# darwin-atlas-module.net
KiCad netlist of a schematic drawn in EAGLE
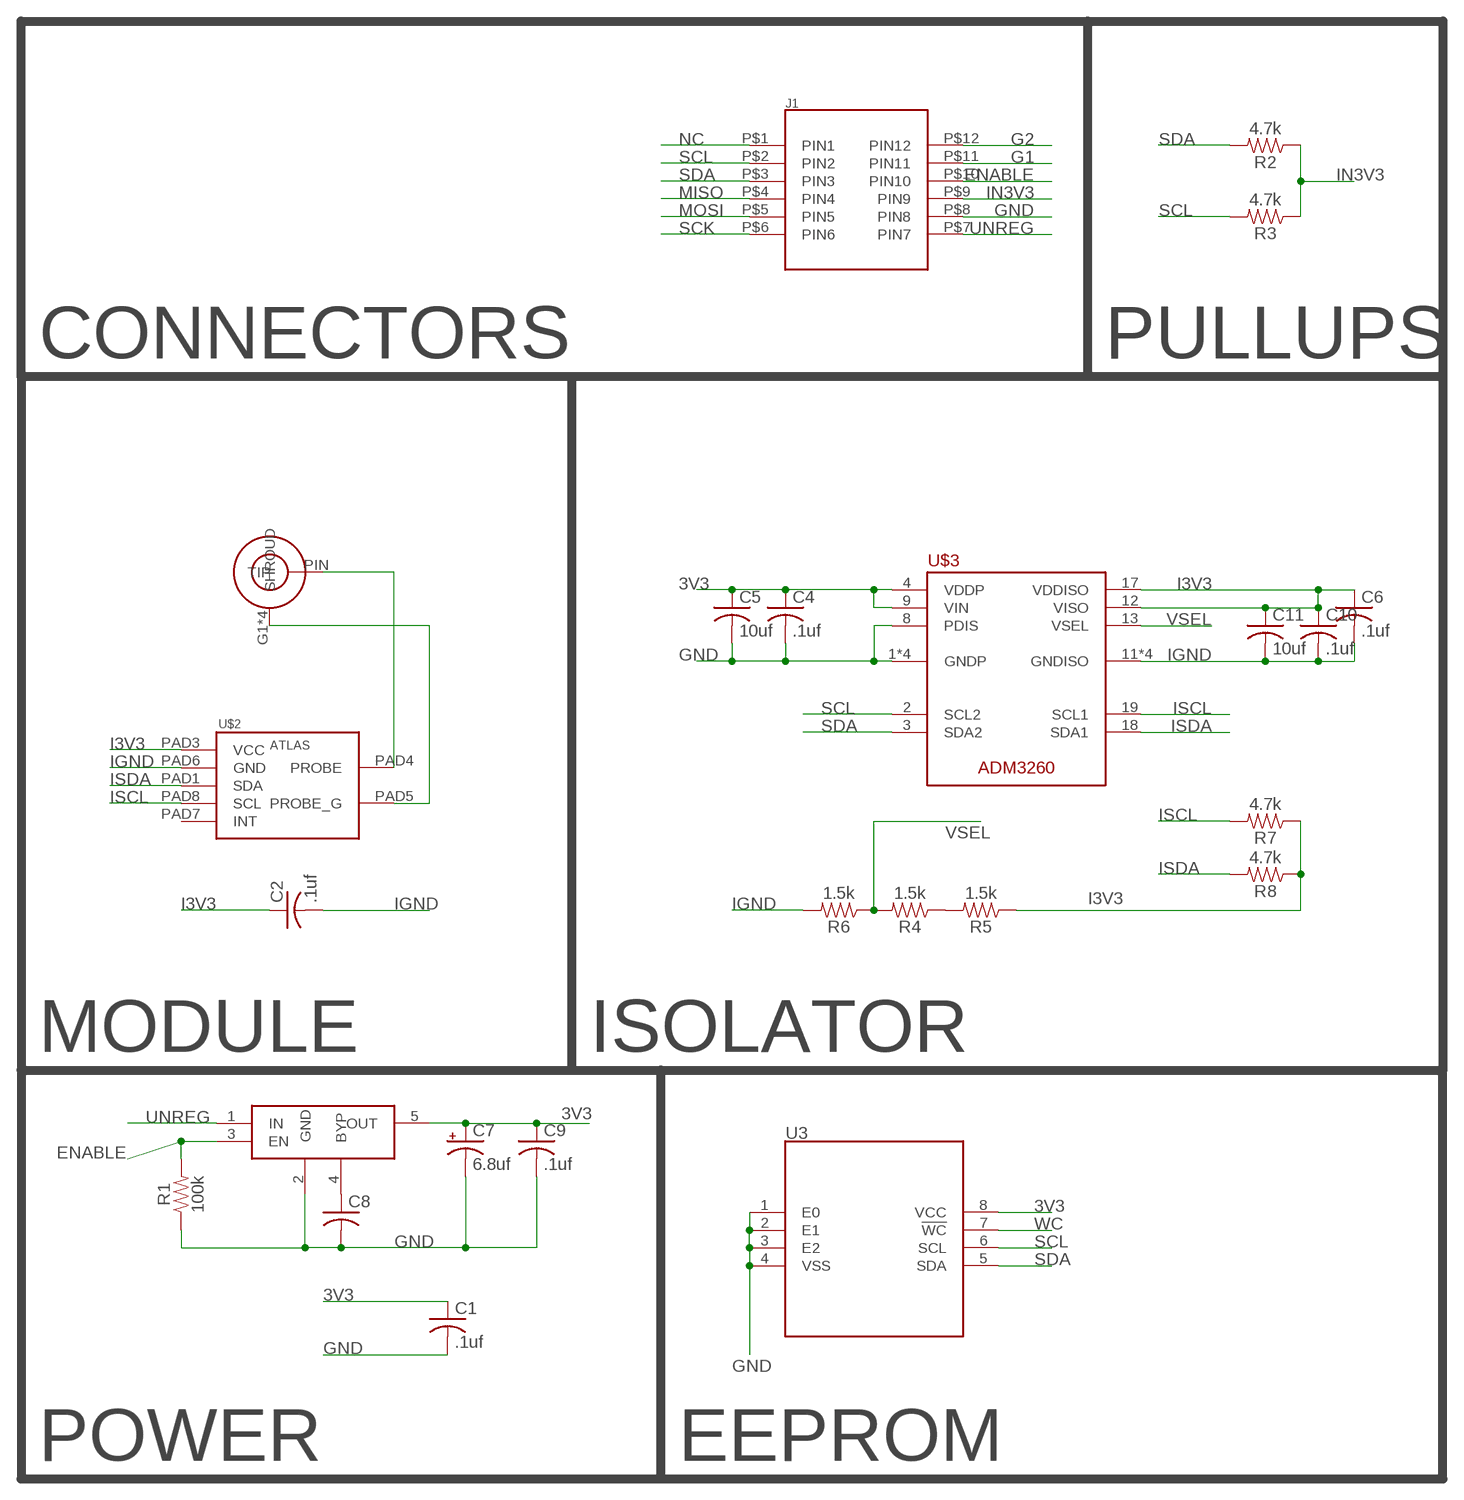
[diagram p0: schematic, sheet 1]

(export (version "E")
  (design (tool "Eeschema 10.0.6"))
  (components
    (comp (ref "C1")
      (value ".1uf")
      (footprint "eagle-import:C0603K")
      (libsource (lib "eagle-import") (part "C-USC0603K"))
    )
    (comp (ref "C2")
      (value ".1uf")
      (footprint "eagle-import:C0603K")
      (libsource (lib "eagle-import") (part "C-USC0603K"))
    )
    (comp (ref "C4")
      (value ".1uf")
      (footprint "eagle-import:C0603K")
      (libsource (lib "eagle-import") (part "C-USC0603K"))
    )
    (comp (ref "C5")
      (value "10uf")
      (footprint "eagle-import:C0603K")
      (libsource (lib "eagle-import") (part "C-USC0603K"))
    )
    (comp (ref "C6")
      (value ".1uf")
      (footprint "eagle-import:C0603K")
      (libsource (lib "eagle-import") (part "C-USC0603K"))
    )
    (comp (ref "C7")
      (value "6.8uf")
      (footprint "eagle-import:A_3216-18R")
      (libsource (lib "eagle-import") (part "CPOL-USA/3216-18R"))
    )
    (comp (ref "C8")
      (value "C-USC0603K")
      (footprint "eagle-import:C0603K")
      (libsource (lib "eagle-import") (part "C-USC0603K"))
    )
    (comp (ref "C9")
      (value ".1uf")
      (footprint "eagle-import:C0603K")
      (libsource (lib "eagle-import") (part "C-USC0603K"))
    )
    (comp (ref "C10")
      (value ".1uf")
      (footprint "eagle-import:C0603K")
      (libsource (lib "eagle-import") (part "C-USC0603K"))
    )
    (comp (ref "C11")
      (value "10uf")
      (footprint "eagle-import:C0603K")
      (libsource (lib "eagle-import") (part "C-USC0603K"))
    )
    (comp (ref "J1")
      (value "2X6-HEADERS")
      (footprint "eagle-import:M20-7810645")
      (libsource (lib "eagle-import") (part "2X6-HEADERS"))
    )
    (comp (ref "R1")
      (value "100k")
      (footprint "eagle-import:0603")
      (libsource (lib "eagle-import") (part "100KOHM-0603-1/10W-1%"))
    )
    (comp (ref "R2")
      (value "4.7k")
      (footprint "eagle-import:0603")
      (libsource (lib "eagle-import") (part "100KOHM-0603-1/10W-1%"))
    )
    (comp (ref "R3")
      (value "4.7k")
      (footprint "eagle-import:0603")
      (libsource (lib "eagle-import") (part "100KOHM-0603-1/10W-1%"))
    )
    (comp (ref "R4")
      (value "1.5k")
      (footprint "eagle-import:0603")
      (libsource (lib "eagle-import") (part "100KOHM-0603-1/10W-1%"))
    )
    (comp (ref "R5")
      (value "1.5k")
      (footprint "eagle-import:0603")
      (libsource (lib "eagle-import") (part "100KOHM-0603-1/10W-1%"))
    )
    (comp (ref "R6")
      (value "1.5k")
      (footprint "eagle-import:0603")
      (libsource (lib "eagle-import") (part "100KOHM-0603-1/10W-1%"))
    )
    (comp (ref "R7")
      (value "4.7k")
      (footprint "eagle-import:0603")
      (libsource (lib "eagle-import") (part "100KOHM-0603-1/10W-1%"))
    )
    (comp (ref "R8")
      (value "4.7k")
      (footprint "eagle-import:0603")
      (libsource (lib "eagle-import") (part "100KOHM-0603-1/10W-1%"))
    )
    (comp (ref "U$1")
      (value "5-1814832-1")
      (footprint "eagle-import:5-1814832-1")
      (libsource (lib "eagle-import") (part "5-1814832-1"))
    )
    (comp (ref "U$2")
      (value "ATLAS10P")
      (footprint "eagle-import:ATLAS-10P")
      (libsource (lib "eagle-import") (part "ATLAS10P"))
    )
    (comp (ref "U$3")
      (value "ADM3260")
      (footprint "eagle-import:SOP65P780X200-20")
      (libsource (lib "eagle-import") (part "ADM3260"))
    )
    (comp (ref "U$4")
      (value "MIC5219-3.3YM5-TR")
      (footprint "eagle-import:SOT95P280X145-5")
      (libsource (lib "eagle-import") (part "MIC5219-3.3YM5-TR"))
    )
    (comp (ref "U3")
      (value "M24C02-WMN6TP")
      (footprint "eagle-import:SOIC127P600X175-8")
      (libsource (lib "eagle-import") (part "M24C02-WMN6TP"))
    )
  )
  (nets
    (net (code "1") (name "/3V3") (class "Default")
      (node (ref "C1") (pin "1") (pinfunction "1_1") (pintype "passive"))
      (node (ref "C4") (pin "1") (pinfunction "1_1") (pintype "passive"))
      (node (ref "C5") (pin "1") (pinfunction "1_1") (pintype "passive"))
      (node (ref "C7") (pin "+") (pinfunction "+_+") (pintype "passive"))
      (node (ref "C9") (pin "1") (pinfunction "1_1") (pintype "passive"))
      (node (ref "U$3") (pin "4") (pinfunction "VDDP_4") (pintype "bidirectional"))
      (node (ref "U$3") (pin "9") (pinfunction "VIN_9") (pintype "bidirectional"))
      (node (ref "U$4") (pin "5") (pinfunction "OUT_5") (pintype "bidirectional"))
      (node (ref "U3") (pin "8") (pinfunction "VCC_8") (pintype "bidirectional"))
    )
    (net (code "2") (name "/ENABLE") (class "Default")
      (node (ref "J1") (pin "P$10") (pinfunction "PIN10_P$10") (pintype "bidirectional"))
      (node (ref "R1") (pin "2") (pinfunction "2_2") (pintype "passive"))
      (node (ref "U$4") (pin "3") (pinfunction "EN_3") (pintype "bidirectional"))
    )
    (net (code "3") (name "/G1") (class "Default")
      (node (ref "J1") (pin "P$11") (pinfunction "PIN11_P$11") (pintype "bidirectional"))
    )
    (net (code "4") (name "/G2") (class "Default")
      (node (ref "J1") (pin "P$12") (pinfunction "PIN12_P$12") (pintype "bidirectional"))
    )
    (net (code "5") (name "/GND") (class "Default")
      (node (ref "C1") (pin "2") (pinfunction "2_2") (pintype "passive"))
      (node (ref "C4") (pin "2") (pinfunction "2_2") (pintype "passive"))
      (node (ref "C5") (pin "2") (pinfunction "2_2") (pintype "passive"))
      (node (ref "C7") (pin "-") (pinfunction "-_-") (pintype "passive"))
      (node (ref "C8") (pin "2") (pinfunction "2_2") (pintype "passive"))
      (node (ref "C9") (pin "2") (pinfunction "2_2") (pintype "passive"))
      (node (ref "J1") (pin "P$8") (pinfunction "PIN8_P$8") (pintype "bidirectional"))
      (node (ref "R1") (pin "1") (pinfunction "1_1") (pintype "passive"))
      (node (ref "U$3") (pin "1") (pinfunction "GNDP_1") (pintype "bidirectional"))
      (node (ref "U$3") (pin "10") (pinfunction "GNDP_10") (pintype "bidirectional"))
      (node (ref "U$3") (pin "5") (pinfunction "GNDP_5") (pintype "bidirectional"))
      (node (ref "U$3") (pin "7") (pinfunction "GNDP_7") (pintype "bidirectional"))
      (node (ref "U$3") (pin "8") (pinfunction "PDIS_8") (pintype "bidirectional"))
      (node (ref "U$4") (pin "2") (pinfunction "GND_2") (pintype "bidirectional"))
      (node (ref "U3") (pin "1") (pinfunction "E0_1") (pintype "bidirectional"))
      (node (ref "U3") (pin "2") (pinfunction "E1_2") (pintype "bidirectional"))
      (node (ref "U3") (pin "3") (pinfunction "E2_3") (pintype "bidirectional"))
      (node (ref "U3") (pin "4") (pinfunction "VSS_4") (pintype "bidirectional"))
    )
    (net (code "6") (name "/I3V3") (class "Default")
      (node (ref "C10") (pin "1") (pinfunction "1_1") (pintype "passive"))
      (node (ref "C11") (pin "1") (pinfunction "1_1") (pintype "passive"))
      (node (ref "C2") (pin "1") (pinfunction "1_1") (pintype "passive"))
      (node (ref "C6") (pin "1") (pinfunction "1_1") (pintype "passive"))
      (node (ref "R5") (pin "1") (pinfunction "1_1") (pintype "passive"))
      (node (ref "R7") (pin "1") (pinfunction "1_1") (pintype "passive"))
      (node (ref "R8") (pin "1") (pinfunction "1_1") (pintype "passive"))
      (node (ref "U$2") (pin "PAD3") (pinfunction "VCC_PAD3") (pintype "bidirectional"))
      (node (ref "U$3") (pin "12") (pinfunction "VISO_12") (pintype "bidirectional"))
      (node (ref "U$3") (pin "17") (pinfunction "VDDISO_17") (pintype "bidirectional"))
    )
    (net (code "7") (name "/IGND") (class "Default")
      (node (ref "C10") (pin "2") (pinfunction "2_2") (pintype "passive"))
      (node (ref "C11") (pin "2") (pinfunction "2_2") (pintype "passive"))
      (node (ref "C2") (pin "2") (pinfunction "2_2") (pintype "passive"))
      (node (ref "C6") (pin "2") (pinfunction "2_2") (pintype "passive"))
      (node (ref "R6") (pin "2") (pinfunction "2_2") (pintype "passive"))
      (node (ref "U$2") (pin "PAD6") (pinfunction "GND_PAD6") (pintype "bidirectional"))
      (node (ref "U$3") (pin "11") (pinfunction "GNDISO_11") (pintype "bidirectional"))
      (node (ref "U$3") (pin "14") (pinfunction "GNDISO_14") (pintype "bidirectional"))
      (node (ref "U$3") (pin "16") (pinfunction "GNDISO_16") (pintype "bidirectional"))
      (node (ref "U$3") (pin "20") (pinfunction "GNDISO_20") (pintype "bidirectional"))
    )
    (net (code "8") (name "/IN3V3") (class "Default")
      (node (ref "J1") (pin "P$9") (pinfunction "PIN9_P$9") (pintype "bidirectional"))
      (node (ref "R2") (pin "1") (pinfunction "1_1") (pintype "passive"))
      (node (ref "R3") (pin "1") (pinfunction "1_1") (pintype "passive"))
    )
    (net (code "9") (name "/ISCL") (class "Default")
      (node (ref "R7") (pin "2") (pinfunction "2_2") (pintype "passive"))
      (node (ref "U$2") (pin "PAD8") (pinfunction "SCL_PAD8") (pintype "bidirectional"))
      (node (ref "U$3") (pin "19") (pinfunction "SCL1_19") (pintype "bidirectional"))
    )
    (net (code "10") (name "/ISDA") (class "Default")
      (node (ref "R8") (pin "2") (pinfunction "2_2") (pintype "passive"))
      (node (ref "U$2") (pin "PAD1") (pinfunction "SDA_PAD1") (pintype "bidirectional"))
      (node (ref "U$3") (pin "18") (pinfunction "SDA1_18") (pintype "bidirectional"))
    )
    (net (code "11") (name "/MISO") (class "Default")
      (node (ref "J1") (pin "P$4") (pinfunction "PIN4_P$4") (pintype "bidirectional"))
    )
    (net (code "12") (name "/MOSI") (class "Default")
      (node (ref "J1") (pin "P$5") (pinfunction "PIN5_P$5") (pintype "bidirectional"))
    )
    (net (code "13") (name "/NC") (class "Default")
      (node (ref "J1") (pin "P$1") (pinfunction "PIN1_P$1") (pintype "bidirectional"))
    )
    (net (code "14") (name "/SCK") (class "Default")
      (node (ref "J1") (pin "P$6") (pinfunction "PIN6_P$6") (pintype "bidirectional"))
    )
    (net (code "15") (name "/SCL") (class "Default")
      (node (ref "J1") (pin "P$2") (pinfunction "PIN2_P$2") (pintype "bidirectional"))
      (node (ref "R3") (pin "2") (pinfunction "2_2") (pintype "passive"))
      (node (ref "U$3") (pin "2") (pinfunction "SCL2_2") (pintype "bidirectional"))
      (node (ref "U3") (pin "6") (pinfunction "SCL_6") (pintype "bidirectional"))
    )
    (net (code "16") (name "/SDA") (class "Default")
      (node (ref "J1") (pin "P$3") (pinfunction "PIN3_P$3") (pintype "bidirectional"))
      (node (ref "R2") (pin "2") (pinfunction "2_2") (pintype "passive"))
      (node (ref "U$3") (pin "3") (pinfunction "SDA2_3") (pintype "bidirectional"))
      (node (ref "U3") (pin "5") (pinfunction "SDA_5") (pintype "bidirectional"))
    )
    (net (code "17") (name "/UNREG") (class "Default")
      (node (ref "J1") (pin "P$7") (pinfunction "PIN7_P$7") (pintype "bidirectional"))
      (node (ref "U$4") (pin "1") (pinfunction "IN_1") (pintype "bidirectional"))
    )
    (net (code "18") (name "/VSEL") (class "Default")
      (node (ref "R4") (pin "2") (pinfunction "2_2") (pintype "passive"))
      (node (ref "R6") (pin "1") (pinfunction "1_1") (pintype "passive"))
      (node (ref "U$3") (pin "13") (pinfunction "VSEL_13") (pintype "bidirectional"))
    )
    (net (code "19") (name "/WC") (class "Default")
      (node (ref "U3") (pin "7") (pinfunction "~{WC}_7") (pintype "bidirectional"))
    )
    (net (code "20") (name "Net-(R4-Pad1)") (class "Default")
      (node (ref "R4") (pin "1") (pinfunction "1_1") (pintype "passive"))
      (node (ref "R5") (pin "2") (pinfunction "2_2") (pintype "passive"))
    )
    (net (code "21") (name "Net-(U$1-TIP)") (class "Default")
      (node (ref "U$1") (pin "PIN") (pinfunction "TIP_PIN") (pintype "bidirectional"))
      (node (ref "U$2") (pin "PAD4") (pinfunction "PROBE_PAD4") (pintype "bidirectional"))
    )
    (net (code "22") (name "Net-(U$2-PROBE_G)") (class "Default")
      (node (ref "U$1") (pin "G1") (pinfunction "SHROUD_G1") (pintype "bidirectional"))
      (node (ref "U$1") (pin "G2") (pinfunction "SHROUD_G2") (pintype "bidirectional"))
      (node (ref "U$1") (pin "G3") (pinfunction "SHROUD_G3") (pintype "bidirectional"))
      (node (ref "U$1") (pin "G4") (pinfunction "SHROUD_G4") (pintype "bidirectional"))
      (node (ref "U$2") (pin "PAD5") (pinfunction "PROBE_G_PAD5") (pintype "bidirectional"))
    )
    (net (code "23") (name "Net-(U$4-BYP)") (class "Default")
      (node (ref "C8") (pin "1") (pinfunction "1_1") (pintype "passive"))
      (node (ref "U$4") (pin "4") (pinfunction "BYP_4") (pintype "bidirectional"))
    )
    (net (code "24") (name "unconnected-(U$2-INT-PadPAD7)") (class "Default")
      (node (ref "U$2") (pin "PAD7") (pinfunction "INT_PAD7") (pintype "bidirectional"))
    )
  )
)
